# STMH7.net
KiCad netlist of a schematic drawn in Altium Designer
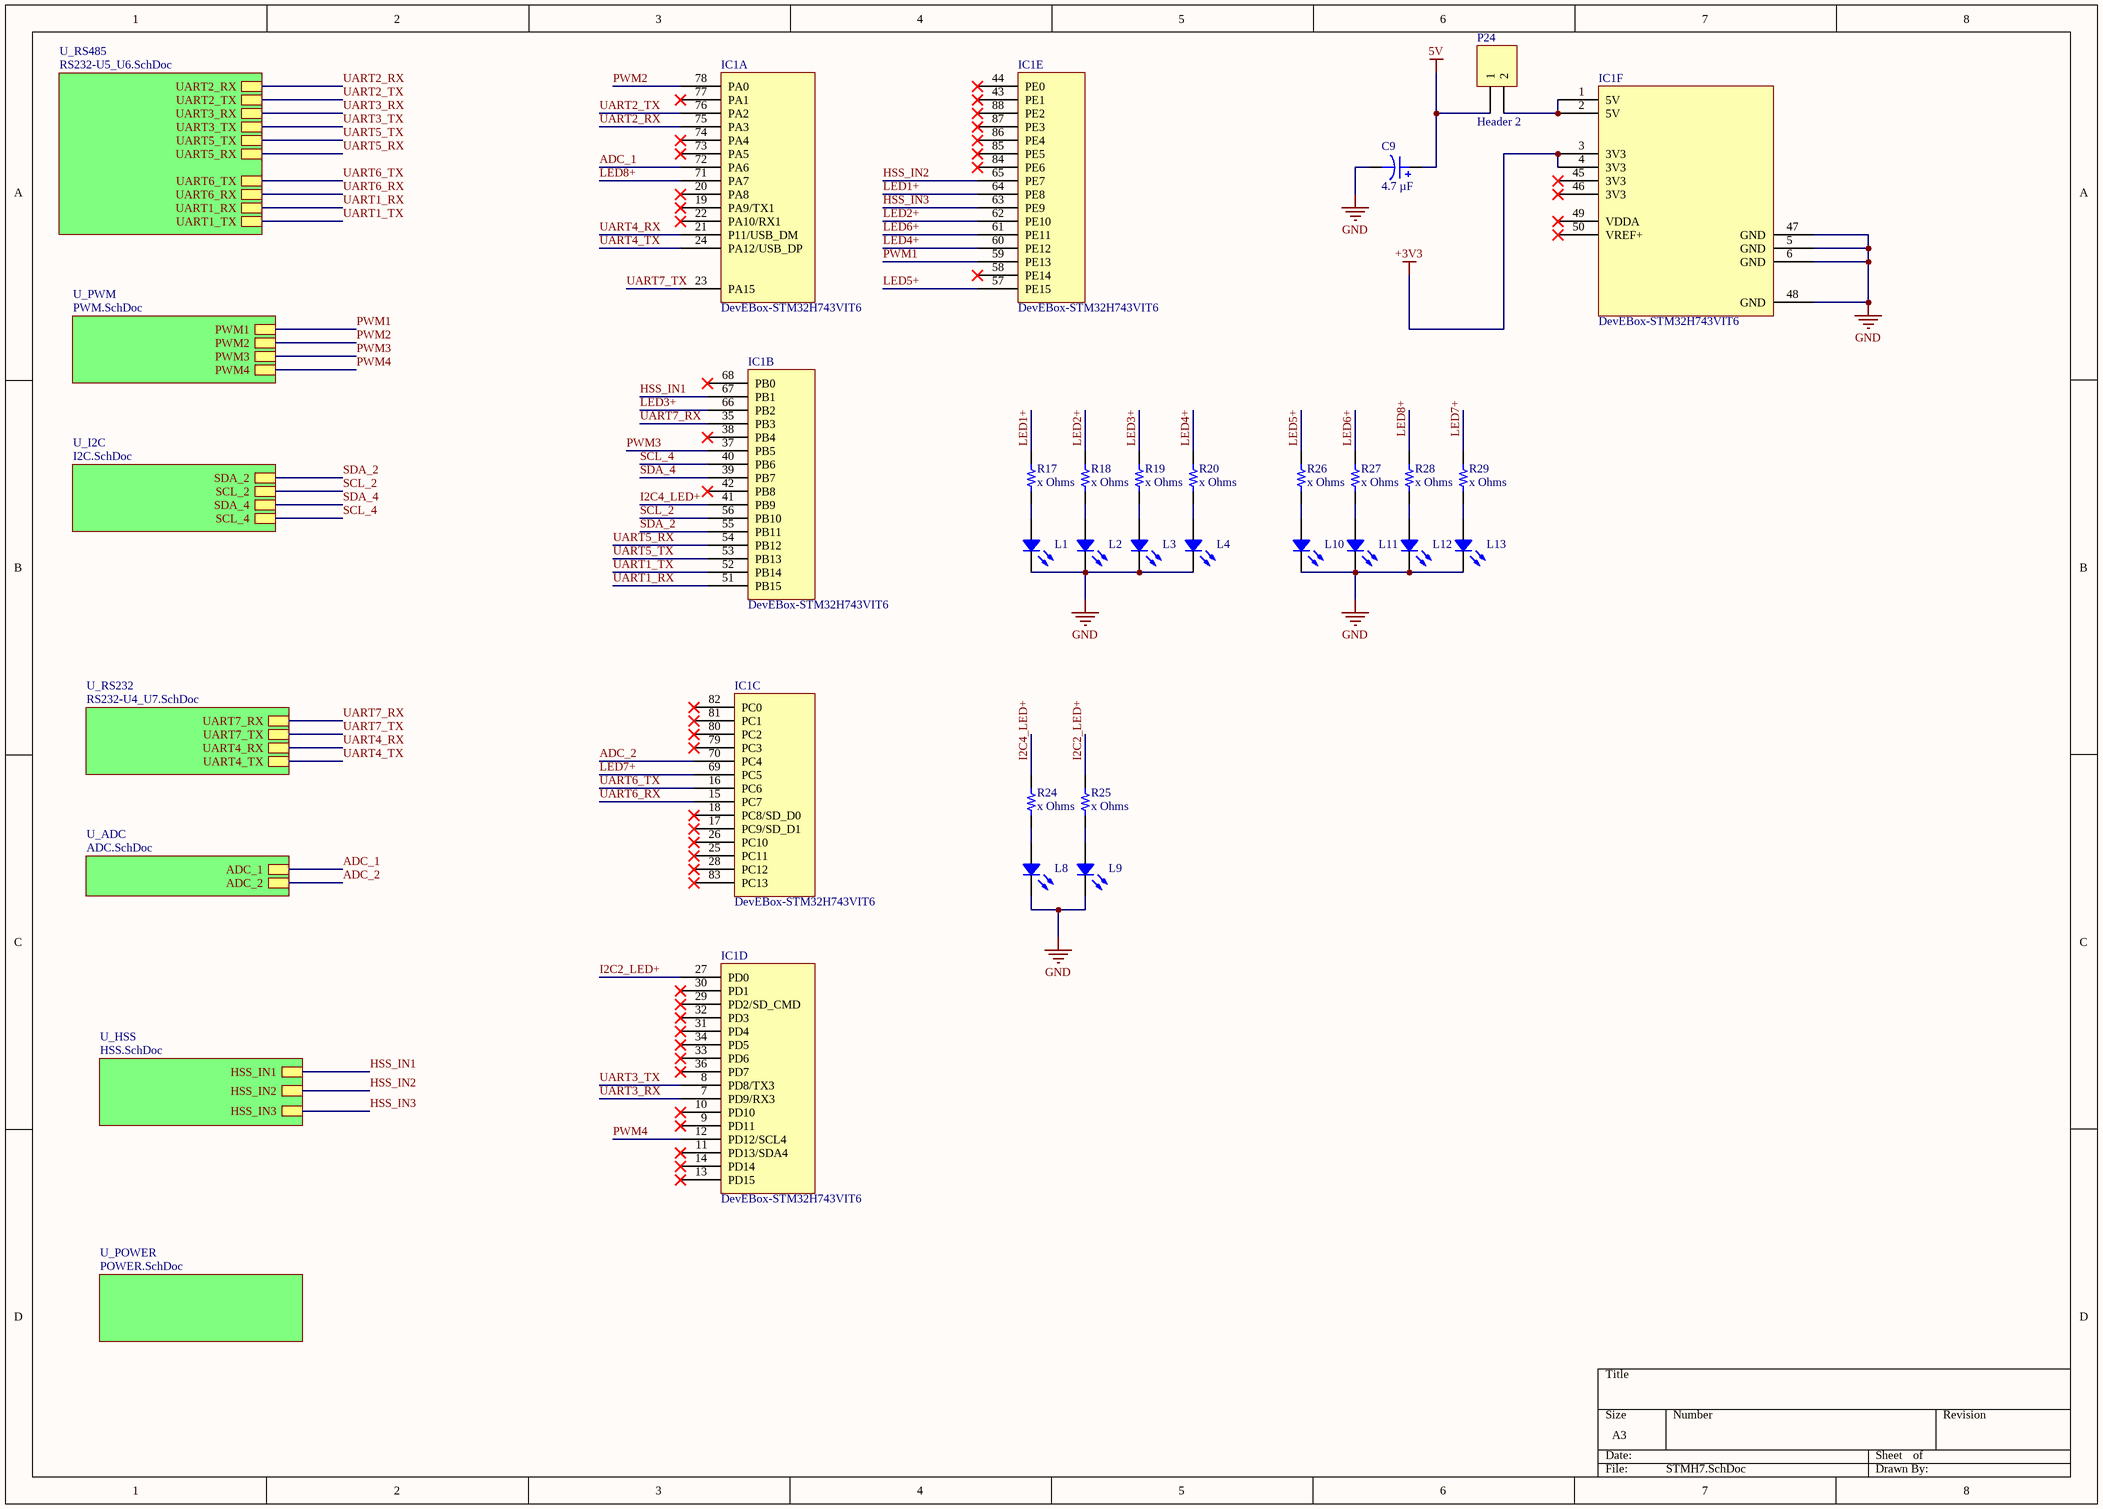
[diagram p0: STMH7.SchDoc]

(export (version "E")
  (design (tool "Eeschema 10.0.6"))
  (components
    (comp (ref "C9")
      (value "4.7 µF")
      (footprint "CAP ALSMD 4.3MM H5.4MM")
      (description "CAP ALUM 4.7UF 20% 35V SMD")
      (fields
        (field (name "PART NUMBER") "EMVE350ADA4R7MD55G")
        (field (name "MANUFACTURER") "United Chemi-Con")
      )
      (libsource (lib "Celestial Altium Library - altium_library") (part "Polarised Capacitor"))
    )
    (comp (ref "IC1")
      (value "DevEBox-STM32H743VIT6")
      (footprint "DevEBox-STM32H743VIT6")
      (libsource (lib "Schlib1") (part "DevEBox-STM32H743VIT6"))
    )
    (comp (ref "L1") (value "LED_SMD") (footprint "LED_SMD") (libsource (lib "Schlib1") (part "LED_SMD")))
    (comp (ref "L2") (value "LED_SMD") (footprint "LED_SMD") (libsource (lib "Schlib1") (part "LED_SMD")))
    (comp (ref "L3") (value "LED_SMD") (footprint "LED_SMD") (libsource (lib "Schlib1") (part "LED_SMD")))
    (comp (ref "L4") (value "LED_SMD") (footprint "LED_SMD") (libsource (lib "Schlib1") (part "LED_SMD")))
    (comp (ref "L8") (value "LED_SMD") (footprint "LED_SMD") (libsource (lib "Schlib1") (part "LED_SMD")))
    (comp (ref "L9") (value "LED_SMD") (footprint "LED_SMD") (libsource (lib "Schlib1") (part "LED_SMD")))
    (comp (ref "L10") (value "LED_SMD") (footprint "LED_SMD") (libsource (lib "Schlib1") (part "LED_SMD")))
    (comp (ref "L11") (value "LED_SMD") (footprint "LED_SMD") (libsource (lib "Schlib1") (part "LED_SMD")))
    (comp (ref "L12") (value "LED_SMD") (footprint "LED_SMD") (libsource (lib "Schlib1") (part "LED_SMD")))
    (comp (ref "L13") (value "LED_SMD") (footprint "LED_SMD") (libsource (lib "Schlib1") (part "LED_SMD")))
    (comp (ref "P24")
      (value "Header 2")
      (footprint "HDR1X2")
      (description "Header, 2-Pin")
      (fields (field (name "PUBLISHER") "Altium Limited"))
      (libsource (lib "Miscellaneous Connectors") (part "Header 2"))
    )
    (comp (ref "R17")
      (value "x Ohms")
      (footprint "RES 1206_3216 RF")
      (description "RES SMD 49.9 OHM 0.1% 1/4W 1206")
      (fields (field (name "PART NUMBER") "RT1206BRD0749R9L") (field (name "MANUFACTURER") "Yageo"))
      (libsource (lib "Celestial Altium Library - altium_library") (part "Resistor"))
    )
    (comp (ref "R18")
      (value "x Ohms")
      (footprint "RES 1206_3216 RF")
      (description "RES SMD 49.9 OHM 0.1% 1/4W 1206")
      (fields (field (name "PART NUMBER") "RT1206BRD0749R9L") (field (name "MANUFACTURER") "Yageo"))
      (libsource (lib "Celestial Altium Library - altium_library") (part "Resistor"))
    )
    (comp (ref "R19")
      (value "x Ohms")
      (footprint "RES 1206_3216 RF")
      (description "RES SMD 49.9 OHM 0.1% 1/4W 1206")
      (fields (field (name "PART NUMBER") "RT1206BRD0749R9L") (field (name "MANUFACTURER") "Yageo"))
      (libsource (lib "Celestial Altium Library - altium_library") (part "Resistor"))
    )
    (comp (ref "R20")
      (value "x Ohms")
      (footprint "RES 1206_3216 RF")
      (description "RES SMD 49.9 OHM 0.1% 1/4W 1206")
      (fields (field (name "PART NUMBER") "RT1206BRD0749R9L") (field (name "MANUFACTURER") "Yageo"))
      (libsource (lib "Celestial Altium Library - altium_library") (part "Resistor"))
    )
    (comp (ref "R24")
      (value "x Ohms")
      (footprint "RES 1206_3216 RF")
      (description "RES SMD 49.9 OHM 0.1% 1/4W 1206")
      (fields (field (name "PART NUMBER") "RT1206BRD0749R9L") (field (name "MANUFACTURER") "Yageo"))
      (libsource (lib "Celestial Altium Library - altium_library") (part "Resistor"))
    )
    (comp (ref "R25")
      (value "x Ohms")
      (footprint "RES 1206_3216 RF")
      (description "RES SMD 49.9 OHM 0.1% 1/4W 1206")
      (fields (field (name "PART NUMBER") "RT1206BRD0749R9L") (field (name "MANUFACTURER") "Yageo"))
      (libsource (lib "Celestial Altium Library - altium_library") (part "Resistor"))
    )
    (comp (ref "R26")
      (value "x Ohms")
      (footprint "RES 1206_3216 RF")
      (description "RES SMD 49.9 OHM 0.1% 1/4W 1206")
      (fields (field (name "PART NUMBER") "RT1206BRD0749R9L") (field (name "MANUFACTURER") "Yageo"))
      (libsource (lib "Celestial Altium Library - altium_library") (part "Resistor"))
    )
    (comp (ref "R27")
      (value "x Ohms")
      (footprint "RES 1206_3216 RF")
      (description "RES SMD 49.9 OHM 0.1% 1/4W 1206")
      (fields (field (name "PART NUMBER") "RT1206BRD0749R9L") (field (name "MANUFACTURER") "Yageo"))
      (libsource (lib "Celestial Altium Library - altium_library") (part "Resistor"))
    )
    (comp (ref "R28")
      (value "x Ohms")
      (footprint "RES 1206_3216 RF")
      (description "RES SMD 49.9 OHM 0.1% 1/4W 1206")
      (fields (field (name "PART NUMBER") "RT1206BRD0749R9L") (field (name "MANUFACTURER") "Yageo"))
      (libsource (lib "Celestial Altium Library - altium_library") (part "Resistor"))
    )
    (comp (ref "R29")
      (value "x Ohms")
      (footprint "RES 1206_3216 RF")
      (description "RES SMD 49.9 OHM 0.1% 1/4W 1206")
      (fields (field (name "PART NUMBER") "RT1206BRD0749R9L") (field (name "MANUFACTURER") "Yageo"))
      (libsource (lib "Celestial Altium Library - altium_library") (part "Resistor"))
    )
  )
  (nets
    (net (code "1") (name "+3V3") (class "Default")
      (node (ref "IC1") (pin "3") (pinfunction "3V3_3") (pintype "passive"))
      (node (ref "IC1") (pin "4") (pinfunction "3V3_4") (pintype "passive"))
    )
    (net (code "2") (name "/ADC_1") (class "Default")
      (node (ref "IC1") (pin "72") (pinfunction "PA6_72") (pintype "passive"))
    )
    (net (code "3") (name "/ADC_2") (class "Default")
      (node (ref "IC1") (pin "70") (pinfunction "PC4_70") (pintype "passive"))
    )
    (net (code "4") (name "/HSS_IN1") (class "Default")
      (node (ref "IC1") (pin "67") (pinfunction "PB1_67") (pintype "passive"))
    )
    (net (code "5") (name "/HSS_IN2") (class "Default")
      (node (ref "IC1") (pin "65") (pinfunction "PE7_65") (pintype "passive"))
    )
    (net (code "6") (name "/HSS_IN3") (class "Default")
      (node (ref "IC1") (pin "63") (pinfunction "PE9_63") (pintype "passive"))
    )
    (net (code "7") (name "/I2C2_LED+") (class "Default")
      (node (ref "IC1") (pin "27") (pinfunction "PD0_27") (pintype "passive"))
      (node (ref "R25") (pin "2") (pinfunction "2_2") (pintype "passive"))
    )
    (net (code "8") (name "/I2C4_LED+") (class "Default")
      (node (ref "IC1") (pin "41") (pinfunction "PB9_41") (pintype "passive"))
      (node (ref "R24") (pin "2") (pinfunction "2_2") (pintype "passive"))
    )
    (net (code "9") (name "/LED1+") (class "Default")
      (node (ref "IC1") (pin "64") (pinfunction "PE8_64") (pintype "passive"))
      (node (ref "R17") (pin "2") (pinfunction "2_2") (pintype "passive"))
    )
    (net (code "10") (name "/LED2+") (class "Default")
      (node (ref "IC1") (pin "62") (pinfunction "PE10_62") (pintype "passive"))
      (node (ref "R18") (pin "2") (pinfunction "2_2") (pintype "passive"))
    )
    (net (code "11") (name "/LED3+") (class "Default")
      (node (ref "IC1") (pin "66") (pinfunction "PB2_66") (pintype "passive"))
      (node (ref "R19") (pin "2") (pinfunction "2_2") (pintype "passive"))
    )
    (net (code "12") (name "/LED4+") (class "Default")
      (node (ref "IC1") (pin "60") (pinfunction "PE12_60") (pintype "passive"))
      (node (ref "R20") (pin "2") (pinfunction "2_2") (pintype "passive"))
    )
    (net (code "13") (name "/LED5+") (class "Default")
      (node (ref "IC1") (pin "57") (pinfunction "PE15_57") (pintype "passive"))
      (node (ref "R26") (pin "2") (pinfunction "2_2") (pintype "passive"))
    )
    (net (code "14") (name "/LED6+") (class "Default")
      (node (ref "IC1") (pin "61") (pinfunction "PE11_61") (pintype "passive"))
      (node (ref "R27") (pin "2") (pinfunction "2_2") (pintype "passive"))
    )
    (net (code "15") (name "/LED7+") (class "Default")
      (node (ref "IC1") (pin "69") (pinfunction "PC5_69") (pintype "passive"))
      (node (ref "R29") (pin "2") (pinfunction "2_2") (pintype "passive"))
    )
    (net (code "16") (name "/LED8+") (class "Default")
      (node (ref "IC1") (pin "71") (pinfunction "PA7_71") (pintype "passive"))
      (node (ref "R28") (pin "2") (pinfunction "2_2") (pintype "passive"))
    )
    (net (code "17") (name "/PWM1") (class "Default")
      (node (ref "IC1") (pin "59") (pinfunction "PE13_59") (pintype "passive"))
    )
    (net (code "18") (name "/PWM2") (class "Default")
      (node (ref "IC1") (pin "78") (pinfunction "PA0_78") (pintype "passive"))
    )
    (net (code "19") (name "/PWM3") (class "Default")
      (node (ref "IC1") (pin "37") (pinfunction "PB5_37") (pintype "passive"))
    )
    (net (code "20") (name "/PWM4") (class "Default")
      (node (ref "IC1") (pin "12") (pinfunction "PD12/SCL4_12") (pintype "passive"))
    )
    (net (code "21") (name "/SCL_2") (class "Default")
      (node (ref "IC1") (pin "56") (pinfunction "PB10_56") (pintype "passive"))
    )
    (net (code "22") (name "/SCL_4") (class "Default")
      (node (ref "IC1") (pin "40") (pinfunction "PB6_40") (pintype "passive"))
    )
    (net (code "23") (name "/SDA_2") (class "Default")
      (node (ref "IC1") (pin "55") (pinfunction "PB11_55") (pintype "passive"))
    )
    (net (code "24") (name "/SDA_4") (class "Default")
      (node (ref "IC1") (pin "39") (pinfunction "PB7_39") (pintype "passive"))
    )
    (net (code "25") (name "/UART1_RX") (class "Default")
      (node (ref "IC1") (pin "51") (pinfunction "PB15_51") (pintype "passive"))
    )
    (net (code "26") (name "/UART1_TX") (class "Default")
      (node (ref "IC1") (pin "52") (pinfunction "PB14_52") (pintype "passive"))
    )
    (net (code "27") (name "/UART2_RX") (class "Default")
      (node (ref "IC1") (pin "75") (pinfunction "PA3_75") (pintype "passive"))
    )
    (net (code "28") (name "/UART2_TX") (class "Default")
      (node (ref "IC1") (pin "76") (pinfunction "PA2_76") (pintype "passive"))
    )
    (net (code "29") (name "/UART3_RX") (class "Default")
      (node (ref "IC1") (pin "7") (pinfunction "PD9/RX3_7") (pintype "passive"))
    )
    (net (code "30") (name "/UART3_TX") (class "Default")
      (node (ref "IC1") (pin "8") (pinfunction "PD8/TX3_8") (pintype "passive"))
    )
    (net (code "31") (name "/UART4_RX") (class "Default")
      (node (ref "IC1") (pin "21") (pinfunction "P11/USB_DM_21") (pintype "passive"))
    )
    (net (code "32") (name "/UART4_TX") (class "Default")
      (node (ref "IC1") (pin "24") (pinfunction "PA12/USB_DP_24") (pintype "passive"))
    )
    (net (code "33") (name "/UART5_RX") (class "Default")
      (node (ref "IC1") (pin "54") (pinfunction "PB12_54") (pintype "passive"))
    )
    (net (code "34") (name "/UART5_TX") (class "Default")
      (node (ref "IC1") (pin "53") (pinfunction "PB13_53") (pintype "passive"))
    )
    (net (code "35") (name "/UART6_RX") (class "Default")
      (node (ref "IC1") (pin "15") (pinfunction "PC7_15") (pintype "passive"))
    )
    (net (code "36") (name "/UART6_TX") (class "Default")
      (node (ref "IC1") (pin "16") (pinfunction "PC6_16") (pintype "passive"))
    )
    (net (code "37") (name "/UART7_RX") (class "Default")
      (node (ref "IC1") (pin "35") (pinfunction "PB3_35") (pintype "passive"))
    )
    (net (code "38") (name "/UART7_TX") (class "Default")
      (node (ref "IC1") (pin "23") (pinfunction "PA15_23") (pintype "passive"))
    )
    (net (code "39") (name "5V") (class "Default")
      (node (ref "C9") (pin "1") (pinfunction "1_1") (pintype "passive"))
      (node (ref "P24") (pin "1") (pinfunction "1_1") (pintype "passive"))
    )
    (net (code "40") (name "GND") (class "Default")
      (node (ref "C9") (pin "2") (pinfunction "2_2") (pintype "passive"))
      (node (ref "IC1") (pin "47") (pinfunction "GND_47") (pintype "passive"))
      (node (ref "IC1") (pin "48") (pinfunction "GND_48") (pintype "passive"))
      (node (ref "IC1") (pin "5") (pinfunction "GND_5") (pintype "passive"))
      (node (ref "IC1") (pin "6") (pinfunction "GND_6") (pintype "passive"))
      (node (ref "L1") (pin "2") (pinfunction "2_2") (pintype "passive"))
      (node (ref "L10") (pin "2") (pinfunction "2_2") (pintype "passive"))
      (node (ref "L11") (pin "2") (pinfunction "2_2") (pintype "passive"))
      (node (ref "L12") (pin "2") (pinfunction "2_2") (pintype "passive"))
      (node (ref "L13") (pin "2") (pinfunction "2_2") (pintype "passive"))
      (node (ref "L2") (pin "2") (pinfunction "2_2") (pintype "passive"))
      (node (ref "L3") (pin "2") (pinfunction "2_2") (pintype "passive"))
      (node (ref "L4") (pin "2") (pinfunction "2_2") (pintype "passive"))
      (node (ref "L8") (pin "2") (pinfunction "2_2") (pintype "passive"))
      (node (ref "L9") (pin "2") (pinfunction "2_2") (pintype "passive"))
    )
    (net (code "41") (name "Net-(IC1F-5V-Pad1)") (class "Default")
      (node (ref "IC1") (pin "1") (pinfunction "5V_1") (pintype "passive"))
      (node (ref "IC1") (pin "2") (pinfunction "5V_2") (pintype "passive"))
      (node (ref "P24") (pin "2") (pinfunction "2_2") (pintype "passive"))
    )
    (net (code "42") (name "Net-(L1-Pad1)") (class "Default")
      (node (ref "L1") (pin "1") (pinfunction "1_1") (pintype "passive"))
      (node (ref "R17") (pin "1") (pinfunction "1_1") (pintype "passive"))
    )
    (net (code "43") (name "Net-(L2-Pad1)") (class "Default")
      (node (ref "L2") (pin "1") (pinfunction "1_1") (pintype "passive"))
      (node (ref "R18") (pin "1") (pinfunction "1_1") (pintype "passive"))
    )
    (net (code "44") (name "Net-(L3-Pad1)") (class "Default")
      (node (ref "L3") (pin "1") (pinfunction "1_1") (pintype "passive"))
      (node (ref "R19") (pin "1") (pinfunction "1_1") (pintype "passive"))
    )
    (net (code "45") (name "Net-(L4-Pad1)") (class "Default")
      (node (ref "L4") (pin "1") (pinfunction "1_1") (pintype "passive"))
      (node (ref "R20") (pin "1") (pinfunction "1_1") (pintype "passive"))
    )
    (net (code "46") (name "Net-(L8-Pad1)") (class "Default")
      (node (ref "L8") (pin "1") (pinfunction "1_1") (pintype "passive"))
      (node (ref "R24") (pin "1") (pinfunction "1_1") (pintype "passive"))
    )
    (net (code "47") (name "Net-(L9-Pad1)") (class "Default")
      (node (ref "L9") (pin "1") (pinfunction "1_1") (pintype "passive"))
      (node (ref "R25") (pin "1") (pinfunction "1_1") (pintype "passive"))
    )
    (net (code "48") (name "Net-(L10-Pad1)") (class "Default")
      (node (ref "L10") (pin "1") (pinfunction "1_1") (pintype "passive"))
      (node (ref "R26") (pin "1") (pinfunction "1_1") (pintype "passive"))
    )
    (net (code "49") (name "Net-(L11-Pad1)") (class "Default")
      (node (ref "L11") (pin "1") (pinfunction "1_1") (pintype "passive"))
      (node (ref "R27") (pin "1") (pinfunction "1_1") (pintype "passive"))
    )
    (net (code "50") (name "Net-(L12-Pad1)") (class "Default")
      (node (ref "L12") (pin "1") (pinfunction "1_1") (pintype "passive"))
      (node (ref "R28") (pin "1") (pinfunction "1_1") (pintype "passive"))
    )
    (net (code "51") (name "Net-(L13-Pad1)") (class "Default")
      (node (ref "L13") (pin "1") (pinfunction "1_1") (pintype "passive"))
      (node (ref "R29") (pin "1") (pinfunction "1_1") (pintype "passive"))
    )
    (net (code "52") (name "unconnected-(IC1A-PA1-Pad77)") (class "Default")
      (node (ref "IC1") (pin "77") (pinfunction "PA1_77") (pintype "passive+no_connect"))
    )
    (net (code "53") (name "unconnected-(IC1A-PA4-Pad74)") (class "Default")
      (node (ref "IC1") (pin "74") (pinfunction "PA4_74") (pintype "passive+no_connect"))
    )
    (net (code "54") (name "unconnected-(IC1A-PA5-Pad73)") (class "Default")
      (node (ref "IC1") (pin "73") (pinfunction "PA5_73") (pintype "passive+no_connect"))
    )
    (net (code "55") (name "unconnected-(IC1A-PA8-Pad20)") (class "Default")
      (node (ref "IC1") (pin "20") (pinfunction "PA8_20") (pintype "passive+no_connect"))
    )
    (net (code "56") (name "unconnected-(IC1A-PA9{slash}TX1-Pad19)") (class "Default")
      (node (ref "IC1") (pin "19") (pinfunction "PA9/TX1_19") (pintype "passive+no_connect"))
    )
    (net (code "57") (name "unconnected-(IC1A-PA10{slash}RX1-Pad22)") (class "Default")
      (node (ref "IC1") (pin "22") (pinfunction "PA10/RX1_22") (pintype "passive+no_connect"))
    )
    (net (code "58") (name "unconnected-(IC1B-PB0-Pad68)") (class "Default")
      (node (ref "IC1") (pin "68") (pinfunction "PB0_68") (pintype "passive+no_connect"))
    )
    (net (code "59") (name "unconnected-(IC1B-PB4-Pad38)") (class "Default")
      (node (ref "IC1") (pin "38") (pinfunction "PB4_38") (pintype "passive+no_connect"))
    )
    (net (code "60") (name "unconnected-(IC1B-PB8-Pad42)") (class "Default")
      (node (ref "IC1") (pin "42") (pinfunction "PB8_42") (pintype "passive+no_connect"))
    )
    (net (code "61") (name "unconnected-(IC1C-PC0-Pad82)") (class "Default")
      (node (ref "IC1") (pin "82") (pinfunction "PC0_82") (pintype "passive+no_connect"))
    )
    (net (code "62") (name "unconnected-(IC1C-PC1-Pad81)") (class "Default")
      (node (ref "IC1") (pin "81") (pinfunction "PC1_81") (pintype "passive+no_connect"))
    )
    (net (code "63") (name "unconnected-(IC1C-PC2-Pad80)") (class "Default")
      (node (ref "IC1") (pin "80") (pinfunction "PC2_80") (pintype "passive+no_connect"))
    )
    (net (code "64") (name "unconnected-(IC1C-PC3-Pad79)") (class "Default")
      (node (ref "IC1") (pin "79") (pinfunction "PC3_79") (pintype "passive+no_connect"))
    )
    (net (code "65") (name "unconnected-(IC1C-PC8{slash}SD_D0-Pad18)") (class "Default")
      (node (ref "IC1") (pin "18") (pinfunction "PC8/SD_D0_18") (pintype "passive+no_connect"))
    )
    (net (code "66") (name "unconnected-(IC1C-PC9{slash}SD_D1-Pad17)") (class "Default")
      (node (ref "IC1") (pin "17") (pinfunction "PC9/SD_D1_17") (pintype "passive+no_connect"))
    )
    (net (code "67") (name "unconnected-(IC1C-PC10-Pad26)") (class "Default")
      (node (ref "IC1") (pin "26") (pinfunction "PC10_26") (pintype "passive+no_connect"))
    )
    (net (code "68") (name "unconnected-(IC1C-PC11-Pad25)") (class "Default")
      (node (ref "IC1") (pin "25") (pinfunction "PC11_25") (pintype "passive+no_connect"))
    )
    (net (code "69") (name "unconnected-(IC1C-PC12-Pad28)") (class "Default")
      (node (ref "IC1") (pin "28") (pinfunction "PC12_28") (pintype "passive+no_connect"))
    )
    (net (code "70") (name "unconnected-(IC1C-PC13-Pad83)") (class "Default")
      (node (ref "IC1") (pin "83") (pinfunction "PC13_83") (pintype "passive+no_connect"))
    )
    (net (code "71") (name "unconnected-(IC1D-PD1-Pad30)") (class "Default")
      (node (ref "IC1") (pin "30") (pinfunction "PD1_30") (pintype "passive+no_connect"))
    )
    (net (code "72") (name "unconnected-(IC1D-PD2{slash}SD_CMD-Pad29)") (class "Default")
      (node (ref "IC1") (pin "29") (pinfunction "PD2/SD_CMD_29") (pintype "passive+no_connect"))
    )
    (net (code "73") (name "unconnected-(IC1D-PD3-Pad32)") (class "Default")
      (node (ref "IC1") (pin "32") (pinfunction "PD3_32") (pintype "passive+no_connect"))
    )
    (net (code "74") (name "unconnected-(IC1D-PD4-Pad31)") (class "Default")
      (node (ref "IC1") (pin "31") (pinfunction "PD4_31") (pintype "passive+no_connect"))
    )
    (net (code "75") (name "unconnected-(IC1D-PD5-Pad34)") (class "Default")
      (node (ref "IC1") (pin "34") (pinfunction "PD5_34") (pintype "passive+no_connect"))
    )
    (net (code "76") (name "unconnected-(IC1D-PD6-Pad33)") (class "Default")
      (node (ref "IC1") (pin "33") (pinfunction "PD6_33") (pintype "passive+no_connect"))
    )
    (net (code "77") (name "unconnected-(IC1D-PD7-Pad36)") (class "Default")
      (node (ref "IC1") (pin "36") (pinfunction "PD7_36") (pintype "passive+no_connect"))
    )
    (net (code "78") (name "unconnected-(IC1D-PD10-Pad10)") (class "Default")
      (node (ref "IC1") (pin "10") (pinfunction "PD10_10") (pintype "passive+no_connect"))
    )
    (net (code "79") (name "unconnected-(IC1D-PD11-Pad9)") (class "Default")
      (node (ref "IC1") (pin "9") (pinfunction "PD11_9") (pintype "passive+no_connect"))
    )
    (net (code "80") (name "unconnected-(IC1D-PD13{slash}SDA4-Pad11)") (class "Default")
      (node (ref "IC1") (pin "11") (pinfunction "PD13/SDA4_11") (pintype "passive+no_connect"))
    )
    (net (code "81") (name "unconnected-(IC1D-PD14-Pad14)") (class "Default")
      (node (ref "IC1") (pin "14") (pinfunction "PD14_14") (pintype "passive+no_connect"))
    )
    (net (code "82") (name "unconnected-(IC1D-PD15-Pad13)") (class "Default")
      (node (ref "IC1") (pin "13") (pinfunction "PD15_13") (pintype "passive+no_connect"))
    )
    (net (code "83") (name "unconnected-(IC1E-PE0-Pad44)") (class "Default")
      (node (ref "IC1") (pin "44") (pinfunction "PE0_44") (pintype "passive+no_connect"))
    )
    (net (code "84") (name "unconnected-(IC1E-PE1-Pad43)") (class "Default")
      (node (ref "IC1") (pin "43") (pinfunction "PE1_43") (pintype "passive+no_connect"))
    )
    (net (code "85") (name "unconnected-(IC1E-PE2-Pad88)") (class "Default")
      (node (ref "IC1") (pin "88") (pinfunction "PE2_88") (pintype "passive+no_connect"))
    )
    (net (code "86") (name "unconnected-(IC1E-PE3-Pad87)") (class "Default")
      (node (ref "IC1") (pin "87") (pinfunction "PE3_87") (pintype "passive+no_connect"))
    )
    (net (code "87") (name "unconnected-(IC1E-PE4-Pad86)") (class "Default")
      (node (ref "IC1") (pin "86") (pinfunction "PE4_86") (pintype "passive+no_connect"))
    )
    (net (code "88") (name "unconnected-(IC1E-PE5-Pad85)") (class "Default")
      (node (ref "IC1") (pin "85") (pinfunction "PE5_85") (pintype "passive+no_connect"))
    )
    (net (code "89") (name "unconnected-(IC1E-PE6-Pad84)") (class "Default")
      (node (ref "IC1") (pin "84") (pinfunction "PE6_84") (pintype "passive+no_connect"))
    )
    (net (code "90") (name "unconnected-(IC1E-PE14-Pad58)") (class "Default")
      (node (ref "IC1") (pin "58") (pinfunction "PE14_58") (pintype "passive+no_connect"))
    )
    (net (code "91") (name "unconnected-(IC1F-3V3-Pad45)") (class "Default")
      (node (ref "IC1") (pin "45") (pinfunction "3V3_45") (pintype "passive+no_connect"))
    )
    (net (code "92") (name "unconnected-(IC1F-3V3-Pad46)") (class "Default")
      (node (ref "IC1") (pin "46") (pinfunction "3V3_46") (pintype "passive+no_connect"))
    )
    (net (code "93") (name "unconnected-(IC1F-VDDA-Pad49)") (class "Default")
      (node (ref "IC1") (pin "49") (pinfunction "VDDA_49") (pintype "passive+no_connect"))
    )
    (net (code "94") (name "unconnected-(IC1F-VREF+-Pad50)") (class "Default")
      (node (ref "IC1") (pin "50") (pinfunction "VREF+_50") (pintype "passive+no_connect"))
    )
  )
)
